# SwitchCanaleDP2024.net
KiCad netlist of a schematic drawn in EAGLE
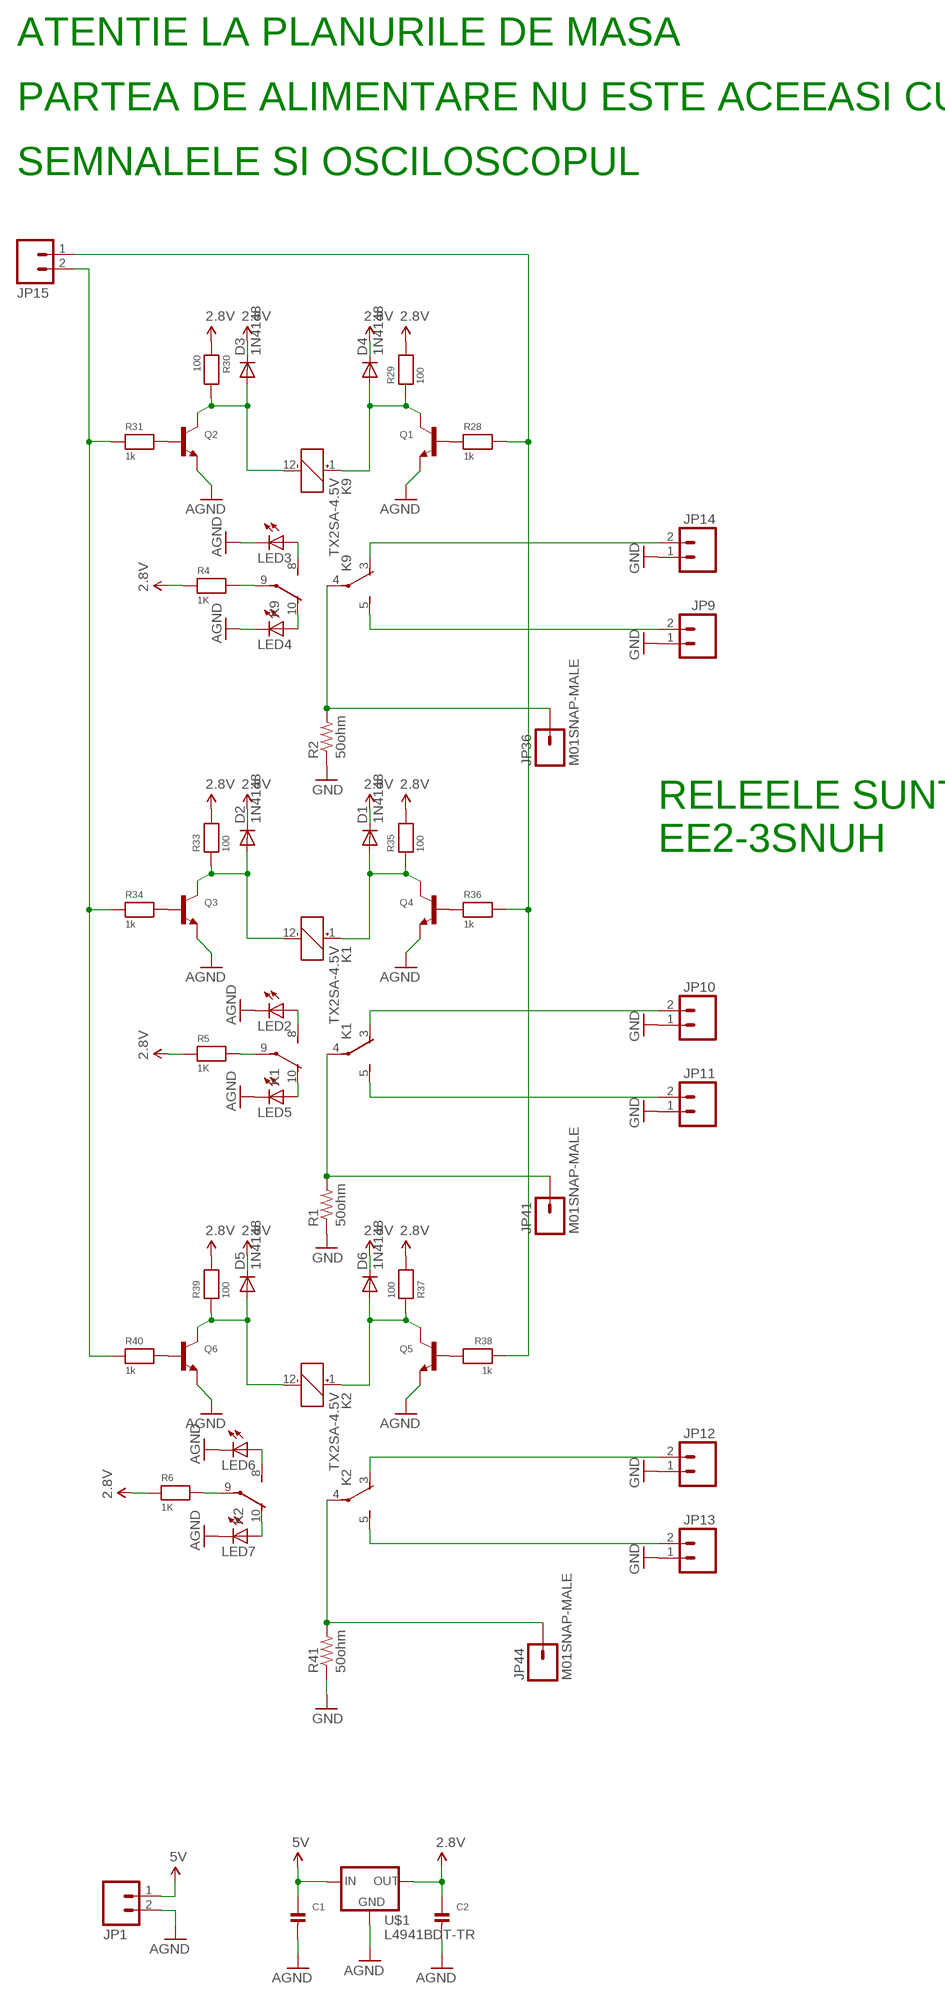
[diagram p0: schematic, sheet 1]

(export (version "E")
  (design (tool "Eeschema 10.0.6"))
  (components
    (comp (ref "C1")
      (value "CAP_CERAMIC1206")
      (footprint "eagle-import:1206")
      (libsource (lib "eagle-import") (part "CAP_CERAMIC1206"))
    )
    (comp (ref "C2")
      (value "CAP_CERAMIC1206")
      (footprint "eagle-import:1206")
      (libsource (lib "eagle-import") (part "CAP_CERAMIC1206"))
    )
    (comp (ref "D1")
      (value "1N4148")
      (footprint "eagle-import:MINIMELF")
      (libsource (lib "eagle-import") (part "DIODE-MINIMELF"))
    )
    (comp (ref "D2")
      (value "1N4148")
      (footprint "eagle-import:MINIMELF")
      (libsource (lib "eagle-import") (part "DIODE-MINIMELF"))
    )
    (comp (ref "D3")
      (value "1N4148")
      (footprint "eagle-import:MINIMELF")
      (libsource (lib "eagle-import") (part "DIODE-MINIMELF"))
    )
    (comp (ref "D4")
      (value "1N4148")
      (footprint "eagle-import:MINIMELF")
      (libsource (lib "eagle-import") (part "DIODE-MINIMELF"))
    )
    (comp (ref "D5")
      (value "1N4148")
      (footprint "eagle-import:MINIMELF")
      (libsource (lib "eagle-import") (part "DIODE-MINIMELF"))
    )
    (comp (ref "D6")
      (value "1N4148")
      (footprint "eagle-import:MINIMELF")
      (libsource (lib "eagle-import") (part "DIODE-MINIMELF"))
    )
    (comp (ref "JP1")
      (value "M025MM")
      (footprint "eagle-import:SCREWTERMINAL-5MM-2")
      (libsource (lib "eagle-import") (part "M025MM"))
    )
    (comp (ref "JP9")
      (value "M025MM")
      (footprint "eagle-import:SCREWTERMINAL-5MM-2")
      (libsource (lib "eagle-import") (part "M025MM"))
    )
    (comp (ref "JP10")
      (value "M025MM")
      (footprint "eagle-import:SCREWTERMINAL-5MM-2")
      (libsource (lib "eagle-import") (part "M025MM"))
    )
    (comp (ref "JP11")
      (value "M025MM")
      (footprint "eagle-import:SCREWTERMINAL-5MM-2")
      (libsource (lib "eagle-import") (part "M025MM"))
    )
    (comp (ref "JP12")
      (value "M025MM")
      (footprint "eagle-import:SCREWTERMINAL-5MM-2")
      (libsource (lib "eagle-import") (part "M025MM"))
    )
    (comp (ref "JP13")
      (value "M025MM")
      (footprint "eagle-import:SCREWTERMINAL-5MM-2")
      (libsource (lib "eagle-import") (part "M025MM"))
    )
    (comp (ref "JP14")
      (value "M025MM")
      (footprint "eagle-import:SCREWTERMINAL-5MM-2")
      (libsource (lib "eagle-import") (part "M025MM"))
    )
    (comp (ref "JP15")
      (value "M025MM")
      (footprint "eagle-import:SCREWTERMINAL-5MM-2")
      (libsource (lib "eagle-import") (part "M025MM"))
    )
    (comp (ref "JP36")
      (value "M01SNAP-MALE")
      (footprint "eagle-import:SNAP-MALE")
      (libsource (lib "eagle-import") (part "M01SNAP-MALE"))
    )
    (comp (ref "JP41")
      (value "M01SNAP-MALE")
      (footprint "eagle-import:SNAP-MALE")
      (libsource (lib "eagle-import") (part "M01SNAP-MALE"))
    )
    (comp (ref "JP44")
      (value "M01SNAP-MALE")
      (footprint "eagle-import:SNAP-MALE")
      (libsource (lib "eagle-import") (part "M01SNAP-MALE"))
    )
    (comp (ref "K1")
      (value "TX2SA-4.5V")
      (footprint "eagle-import:TX2SA")
      (fields (field (name "MF") "AROMAT/ MATSUSHITA"))
      (libsource (lib "eagle-import") (part "TX2?-SA4.5V"))
    )
    (comp (ref "K2")
      (value "TX2SA-4.5V")
      (footprint "eagle-import:TX2SA")
      (fields (field (name "MF") "AROMAT/ MATSUSHITA"))
      (libsource (lib "eagle-import") (part "TX2?-SA4.5V"))
    )
    (comp (ref "K9")
      (value "TX2SA-4.5V")
      (footprint "eagle-import:TX2SA")
      (fields (field (name "MF") "AROMAT/ MATSUSHITA"))
      (libsource (lib "eagle-import") (part "TX2?-SA4.5V"))
    )
    (comp (ref "LED2")
      (value "LEDCHIP-LED0805")
      (footprint "eagle-import:CHIP-LED0805")
      (libsource (lib "eagle-import") (part "LEDCHIP-LED0805"))
    )
    (comp (ref "LED3")
      (value "LEDCHIP-LED0805")
      (footprint "eagle-import:CHIP-LED0805")
      (libsource (lib "eagle-import") (part "LEDCHIP-LED0805"))
    )
    (comp (ref "LED4")
      (value "LEDCHIP-LED0805")
      (footprint "eagle-import:CHIP-LED0805")
      (libsource (lib "eagle-import") (part "LEDCHIP-LED0805"))
    )
    (comp (ref "LED5")
      (value "LEDCHIP-LED0805")
      (footprint "eagle-import:CHIP-LED0805")
      (libsource (lib "eagle-import") (part "LEDCHIP-LED0805"))
    )
    (comp (ref "LED6")
      (value "LEDCHIP-LED0805")
      (footprint "eagle-import:CHIP-LED0805")
      (libsource (lib "eagle-import") (part "LEDCHIP-LED0805"))
    )
    (comp (ref "LED7")
      (value "LEDCHIP-LED0805")
      (footprint "eagle-import:CHIP-LED0805")
      (libsource (lib "eagle-import") (part "LEDCHIP-LED0805"))
    )
    (comp (ref "Q1")
      (value "TRANSISTOR_NPNWAVE")
      (footprint "eagle-import:SOT23-W")
      (libsource (lib "eagle-import") (part "TRANSISTOR_NPNWAVE"))
    )
    (comp (ref "Q2")
      (value "TRANSISTOR_NPNWAVE")
      (footprint "eagle-import:SOT23-W")
      (libsource (lib "eagle-import") (part "TRANSISTOR_NPNWAVE"))
    )
    (comp (ref "Q3")
      (value "TRANSISTOR_NPNWAVE")
      (footprint "eagle-import:SOT23-W")
      (libsource (lib "eagle-import") (part "TRANSISTOR_NPNWAVE"))
    )
    (comp (ref "Q4")
      (value "TRANSISTOR_NPNWAVE")
      (footprint "eagle-import:SOT23-W")
      (libsource (lib "eagle-import") (part "TRANSISTOR_NPNWAVE"))
    )
    (comp (ref "Q5")
      (value "TRANSISTOR_NPNWAVE")
      (footprint "eagle-import:SOT23-W")
      (libsource (lib "eagle-import") (part "TRANSISTOR_NPNWAVE"))
    )
    (comp (ref "Q6")
      (value "TRANSISTOR_NPNWAVE")
      (footprint "eagle-import:SOT23-W")
      (libsource (lib "eagle-import") (part "TRANSISTOR_NPNWAVE"))
    )
    (comp (ref "R1")
      (value "50ohm")
      (footprint "eagle-import:1206")
      (libsource (lib "eagle-import") (part "RESISTOR1206"))
    )
    (comp (ref "R2")
      (value "50ohm")
      (footprint "eagle-import:1206")
      (libsource (lib "eagle-import") (part "RESISTOR1206"))
    )
    (comp (ref "R4")
      (value "1K")
      (footprint "eagle-import:_0805MP")
      (libsource (lib "eagle-import") (part "RESISTOR_0805MP"))
    )
    (comp (ref "R5")
      (value "1K")
      (footprint "eagle-import:_0805MP")
      (libsource (lib "eagle-import") (part "RESISTOR_0805MP"))
    )
    (comp (ref "R6")
      (value "1K")
      (footprint "eagle-import:_0805MP")
      (libsource (lib "eagle-import") (part "RESISTOR_0805MP"))
    )
    (comp (ref "R28")
      (value "1k")
      (footprint "eagle-import:_0805MP")
      (libsource (lib "eagle-import") (part "RESISTOR_0805MP"))
    )
    (comp (ref "R29")
      (value "100")
      (footprint "eagle-import:_0805MP")
      (libsource (lib "eagle-import") (part "RESISTOR_0805MP"))
    )
    (comp (ref "R30")
      (value "100")
      (footprint "eagle-import:_0805MP")
      (libsource (lib "eagle-import") (part "RESISTOR_0805MP"))
    )
    (comp (ref "R31")
      (value "1k")
      (footprint "eagle-import:_0805MP")
      (libsource (lib "eagle-import") (part "RESISTOR_0805MP"))
    )
    (comp (ref "R33")
      (value "100")
      (footprint "eagle-import:_0805MP")
      (libsource (lib "eagle-import") (part "RESISTOR_0805MP"))
    )
    (comp (ref "R34")
      (value "1k")
      (footprint "eagle-import:_0805MP")
      (libsource (lib "eagle-import") (part "RESISTOR_0805MP"))
    )
    (comp (ref "R35")
      (value "100")
      (footprint "eagle-import:_0805MP")
      (libsource (lib "eagle-import") (part "RESISTOR_0805MP"))
    )
    (comp (ref "R36")
      (value "1k")
      (footprint "eagle-import:_0805MP")
      (libsource (lib "eagle-import") (part "RESISTOR_0805MP"))
    )
    (comp (ref "R37")
      (value "100")
      (footprint "eagle-import:_0805MP")
      (libsource (lib "eagle-import") (part "RESISTOR_0805MP"))
    )
    (comp (ref "R38")
      (value "1k")
      (footprint "eagle-import:_0805MP")
      (libsource (lib "eagle-import") (part "RESISTOR_0805MP"))
    )
    (comp (ref "R39")
      (value "100")
      (footprint "eagle-import:_0805MP")
      (libsource (lib "eagle-import") (part "RESISTOR_0805MP"))
    )
    (comp (ref "R40")
      (value "1k")
      (footprint "eagle-import:_0805MP")
      (libsource (lib "eagle-import") (part "RESISTOR_0805MP"))
    )
    (comp (ref "R41")
      (value "50ohm")
      (footprint "eagle-import:1206")
      (libsource (lib "eagle-import") (part "RESISTOR1206"))
    )
    (comp (ref "U$1")
      (value "L4941BDT-TR")
      (footprint "eagle-import:DPAK")
      (libsource (lib "eagle-import") (part "L4941BDT-TR"))
    )
  )
  (nets
    (net (code "1") (name "2.8V") (class "Default")
      (node (ref "C2") (pin "1") (pinfunction "P$1_1") (pintype "passive"))
      (node (ref "D1") (pin "C") (pinfunction "C_C") (pintype "passive"))
      (node (ref "D2") (pin "C") (pinfunction "C_C") (pintype "passive"))
      (node (ref "D3") (pin "C") (pinfunction "C_C") (pintype "passive"))
      (node (ref "D4") (pin "C") (pinfunction "C_C") (pintype "passive"))
      (node (ref "D5") (pin "C") (pinfunction "C_C") (pintype "passive"))
      (node (ref "D6") (pin "C") (pinfunction "C_C") (pintype "passive"))
      (node (ref "R29") (pin "2") (pinfunction "2_2") (pintype "passive"))
      (node (ref "R30") (pin "1") (pinfunction "1_1") (pintype "passive"))
      (node (ref "R33") (pin "2") (pinfunction "2_2") (pintype "passive"))
      (node (ref "R35") (pin "2") (pinfunction "2_2") (pintype "passive"))
      (node (ref "R37") (pin "2") (pinfunction "2_2") (pintype "passive"))
      (node (ref "R39") (pin "2") (pinfunction "2_2") (pintype "passive"))
      (node (ref "R4") (pin "1") (pinfunction "1_1") (pintype "passive"))
      (node (ref "R5") (pin "1") (pinfunction "1_1") (pintype "passive"))
      (node (ref "R6") (pin "1") (pinfunction "1_1") (pintype "passive"))
      (node (ref "U$1") (pin "2") (pinfunction "OUT_2") (pintype "passive"))
    )
    (net (code "2") (name "5V") (class "Default")
      (node (ref "C1") (pin "1") (pinfunction "P$1_1") (pintype "passive"))
      (node (ref "JP1") (pin "1") (pinfunction "1_1") (pintype "passive"))
      (node (ref "U$1") (pin "1") (pinfunction "IN_1") (pintype "input"))
    )
    (net (code "3") (name "AGND") (class "Default")
      (node (ref "C1") (pin "2") (pinfunction "P$2_2") (pintype "passive"))
      (node (ref "C2") (pin "2") (pinfunction "P$2_2") (pintype "passive"))
      (node (ref "JP1") (pin "2") (pinfunction "2_2") (pintype "passive"))
      (node (ref "LED2") (pin "C") (pinfunction "C_C") (pintype "passive"))
      (node (ref "LED3") (pin "C") (pinfunction "C_C") (pintype "passive"))
      (node (ref "LED4") (pin "C") (pinfunction "C_C") (pintype "passive"))
      (node (ref "LED5") (pin "C") (pinfunction "C_C") (pintype "passive"))
      (node (ref "LED6") (pin "C") (pinfunction "C_C") (pintype "passive"))
      (node (ref "LED7") (pin "C") (pinfunction "C_C") (pintype "passive"))
      (node (ref "Q1") (pin "2") (pinfunction "E_2") (pintype "passive"))
      (node (ref "Q2") (pin "2") (pinfunction "E_2") (pintype "passive"))
      (node (ref "Q3") (pin "2") (pinfunction "E_2") (pintype "passive"))
      (node (ref "Q4") (pin "2") (pinfunction "E_2") (pintype "passive"))
      (node (ref "Q5") (pin "2") (pinfunction "E_2") (pintype "passive"))
      (node (ref "Q6") (pin "2") (pinfunction "E_2") (pintype "passive"))
      (node (ref "U$1") (pin "3") (pinfunction "GND_3") (pintype "power_in"))
    )
    (net (code "4") (name "GND") (class "Default")
      (node (ref "JP10") (pin "1") (pinfunction "1_1") (pintype "passive"))
      (node (ref "JP11") (pin "1") (pinfunction "1_1") (pintype "passive"))
      (node (ref "JP12") (pin "1") (pinfunction "1_1") (pintype "passive"))
      (node (ref "JP13") (pin "1") (pinfunction "1_1") (pintype "passive"))
      (node (ref "JP14") (pin "1") (pinfunction "1_1") (pintype "passive"))
      (node (ref "JP9") (pin "1") (pinfunction "1_1") (pintype "passive"))
      (node (ref "R1") (pin "1") (pinfunction "1_1") (pintype "passive"))
      (node (ref "R2") (pin "1") (pinfunction "1_1") (pintype "passive"))
      (node (ref "R41") (pin "1") (pinfunction "1_1") (pintype "passive"))
    )
    (net (code "5") (name "Net-(JP15-Pad1)") (class "Default")
      (node (ref "JP15") (pin "1") (pinfunction "1_1") (pintype "passive"))
      (node (ref "R28") (pin "2") (pinfunction "2_2") (pintype "passive"))
      (node (ref "R36") (pin "2") (pinfunction "2_2") (pintype "passive"))
      (node (ref "R38") (pin "1") (pinfunction "1_1") (pintype "passive"))
    )
    (net (code "6") (name "Net-(JP15-Pad2)") (class "Default")
      (node (ref "JP15") (pin "2") (pinfunction "2_2") (pintype "passive"))
      (node (ref "R31") (pin "1") (pinfunction "1_1") (pintype "passive"))
      (node (ref "R34") (pin "1") (pinfunction "1_1") (pintype "passive"))
      (node (ref "R40") (pin "1") (pinfunction "1_1") (pintype "passive"))
    )
    (net (code "7") (name "Net-(JP36-1)") (class "Default")
      (node (ref "JP36") (pin "2") (pinfunction "1_2") (pintype "passive"))
      (node (ref "K9") (pin "4") (pinfunction "P_4") (pintype "passive"))
      (node (ref "R2") (pin "2") (pinfunction "2_2") (pintype "passive"))
    )
    (net (code "8") (name "Net-(JP41-1)") (class "Default")
      (node (ref "JP41") (pin "2") (pinfunction "1_2") (pintype "passive"))
      (node (ref "K1") (pin "4") (pinfunction "P_4") (pintype "passive"))
      (node (ref "R1") (pin "2") (pinfunction "2_2") (pintype "passive"))
    )
    (net (code "9") (name "Net-(JP44-1)") (class "Default")
      (node (ref "JP44") (pin "2") (pinfunction "1_2") (pintype "passive"))
      (node (ref "K2") (pin "4") (pinfunction "P_4") (pintype "passive"))
      (node (ref "R41") (pin "2") (pinfunction "2_2") (pintype "passive"))
    )
    (net (code "10") (name "Net-(K1A-O)") (class "Default")
      (node (ref "JP10") (pin "2") (pinfunction "2_2") (pintype "passive"))
      (node (ref "K1") (pin "3") (pinfunction "O_3") (pintype "passive"))
    )
    (net (code "11") (name "Net-(K1A-S)") (class "Default")
      (node (ref "JP11") (pin "2") (pinfunction "2_2") (pintype "passive"))
      (node (ref "K1") (pin "5") (pinfunction "S_5") (pintype "passive"))
    )
    (net (code "12") (name "Net-(K1B-O)") (class "Default")
      (node (ref "K1") (pin "10") (pinfunction "O_10") (pintype "passive"))
      (node (ref "LED5") (pin "A") (pinfunction "A_A") (pintype "passive"))
    )
    (net (code "13") (name "Net-(K1B-P)") (class "Default")
      (node (ref "K1") (pin "9") (pinfunction "P_9") (pintype "passive"))
      (node (ref "R5") (pin "2") (pinfunction "2_2") (pintype "passive"))
    )
    (net (code "14") (name "Net-(K1B-S)") (class "Default")
      (node (ref "K1") (pin "8") (pinfunction "S_8") (pintype "passive"))
      (node (ref "LED2") (pin "A") (pinfunction "A_A") (pintype "passive"))
    )
    (net (code "15") (name "Net-(K1C-+)") (class "Default")
      (node (ref "D1") (pin "A") (pinfunction "A_A") (pintype "passive"))
      (node (ref "K1") (pin "1") (pinfunction "+_1") (pintype "passive"))
      (node (ref "Q4") (pin "3") (pinfunction "C_3") (pintype "passive"))
      (node (ref "R35") (pin "1") (pinfunction "1_1") (pintype "passive"))
    )
    (net (code "16") (name "Net-(K1C--)") (class "Default")
      (node (ref "D2") (pin "A") (pinfunction "A_A") (pintype "passive"))
      (node (ref "K1") (pin "12") (pinfunction "-_12") (pintype "passive"))
      (node (ref "Q3") (pin "3") (pinfunction "C_3") (pintype "passive"))
      (node (ref "R33") (pin "1") (pinfunction "1_1") (pintype "passive"))
    )
    (net (code "17") (name "Net-(K2A-O)") (class "Default")
      (node (ref "JP12") (pin "2") (pinfunction "2_2") (pintype "passive"))
      (node (ref "K2") (pin "3") (pinfunction "O_3") (pintype "passive"))
    )
    (net (code "18") (name "Net-(K2A-S)") (class "Default")
      (node (ref "JP13") (pin "2") (pinfunction "2_2") (pintype "passive"))
      (node (ref "K2") (pin "5") (pinfunction "S_5") (pintype "passive"))
    )
    (net (code "19") (name "Net-(K2B-O)") (class "Default")
      (node (ref "K2") (pin "10") (pinfunction "O_10") (pintype "passive"))
      (node (ref "LED7") (pin "A") (pinfunction "A_A") (pintype "passive"))
    )
    (net (code "20") (name "Net-(K2B-P)") (class "Default")
      (node (ref "K2") (pin "9") (pinfunction "P_9") (pintype "passive"))
      (node (ref "R6") (pin "2") (pinfunction "2_2") (pintype "passive"))
    )
    (net (code "21") (name "Net-(K2B-S)") (class "Default")
      (node (ref "K2") (pin "8") (pinfunction "S_8") (pintype "passive"))
      (node (ref "LED6") (pin "A") (pinfunction "A_A") (pintype "passive"))
    )
    (net (code "22") (name "Net-(K2C-+)") (class "Default")
      (node (ref "D6") (pin "A") (pinfunction "A_A") (pintype "passive"))
      (node (ref "K2") (pin "1") (pinfunction "+_1") (pintype "passive"))
      (node (ref "Q5") (pin "3") (pinfunction "C_3") (pintype "passive"))
      (node (ref "R37") (pin "1") (pinfunction "1_1") (pintype "passive"))
    )
    (net (code "23") (name "Net-(K2C--)") (class "Default")
      (node (ref "D5") (pin "A") (pinfunction "A_A") (pintype "passive"))
      (node (ref "K2") (pin "12") (pinfunction "-_12") (pintype "passive"))
      (node (ref "Q6") (pin "3") (pinfunction "C_3") (pintype "passive"))
      (node (ref "R39") (pin "1") (pinfunction "1_1") (pintype "passive"))
    )
    (net (code "24") (name "Net-(K9A-O)") (class "Default")
      (node (ref "JP14") (pin "2") (pinfunction "2_2") (pintype "passive"))
      (node (ref "K9") (pin "3") (pinfunction "O_3") (pintype "passive"))
    )
    (net (code "25") (name "Net-(K9A-S)") (class "Default")
      (node (ref "JP9") (pin "2") (pinfunction "2_2") (pintype "passive"))
      (node (ref "K9") (pin "5") (pinfunction "S_5") (pintype "passive"))
    )
    (net (code "26") (name "Net-(K9B-O)") (class "Default")
      (node (ref "K9") (pin "10") (pinfunction "O_10") (pintype "passive"))
      (node (ref "LED4") (pin "A") (pinfunction "A_A") (pintype "passive"))
    )
    (net (code "27") (name "Net-(K9B-P)") (class "Default")
      (node (ref "K9") (pin "9") (pinfunction "P_9") (pintype "passive"))
      (node (ref "R4") (pin "2") (pinfunction "2_2") (pintype "passive"))
    )
    (net (code "28") (name "Net-(K9B-S)") (class "Default")
      (node (ref "K9") (pin "8") (pinfunction "S_8") (pintype "passive"))
      (node (ref "LED3") (pin "A") (pinfunction "A_A") (pintype "passive"))
    )
    (net (code "29") (name "Net-(K9C-+)") (class "Default")
      (node (ref "D4") (pin "A") (pinfunction "A_A") (pintype "passive"))
      (node (ref "K9") (pin "1") (pinfunction "+_1") (pintype "passive"))
      (node (ref "Q1") (pin "3") (pinfunction "C_3") (pintype "passive"))
      (node (ref "R29") (pin "1") (pinfunction "1_1") (pintype "passive"))
    )
    (net (code "30") (name "Net-(K9C--)") (class "Default")
      (node (ref "D3") (pin "A") (pinfunction "A_A") (pintype "passive"))
      (node (ref "K9") (pin "12") (pinfunction "-_12") (pintype "passive"))
      (node (ref "Q2") (pin "3") (pinfunction "C_3") (pintype "passive"))
      (node (ref "R30") (pin "2") (pinfunction "2_2") (pintype "passive"))
    )
    (net (code "31") (name "Net-(Q1-B)") (class "Default")
      (node (ref "Q1") (pin "1") (pinfunction "B_1") (pintype "passive"))
      (node (ref "R28") (pin "1") (pinfunction "1_1") (pintype "passive"))
    )
    (net (code "32") (name "Net-(Q2-B)") (class "Default")
      (node (ref "Q2") (pin "1") (pinfunction "B_1") (pintype "passive"))
      (node (ref "R31") (pin "2") (pinfunction "2_2") (pintype "passive"))
    )
    (net (code "33") (name "Net-(Q3-B)") (class "Default")
      (node (ref "Q3") (pin "1") (pinfunction "B_1") (pintype "passive"))
      (node (ref "R34") (pin "2") (pinfunction "2_2") (pintype "passive"))
    )
    (net (code "34") (name "Net-(Q4-B)") (class "Default")
      (node (ref "Q4") (pin "1") (pinfunction "B_1") (pintype "passive"))
      (node (ref "R36") (pin "1") (pinfunction "1_1") (pintype "passive"))
    )
    (net (code "35") (name "Net-(Q5-B)") (class "Default")
      (node (ref "Q5") (pin "1") (pinfunction "B_1") (pintype "passive"))
      (node (ref "R38") (pin "2") (pinfunction "2_2") (pintype "passive"))
    )
    (net (code "36") (name "Net-(Q6-B)") (class "Default")
      (node (ref "Q6") (pin "1") (pinfunction "B_1") (pintype "passive"))
      (node (ref "R40") (pin "2") (pinfunction "2_2") (pintype "passive"))
    )
  )
)
